# WAN.net
KiCad netlist of a schematic drawn in Altium Designer
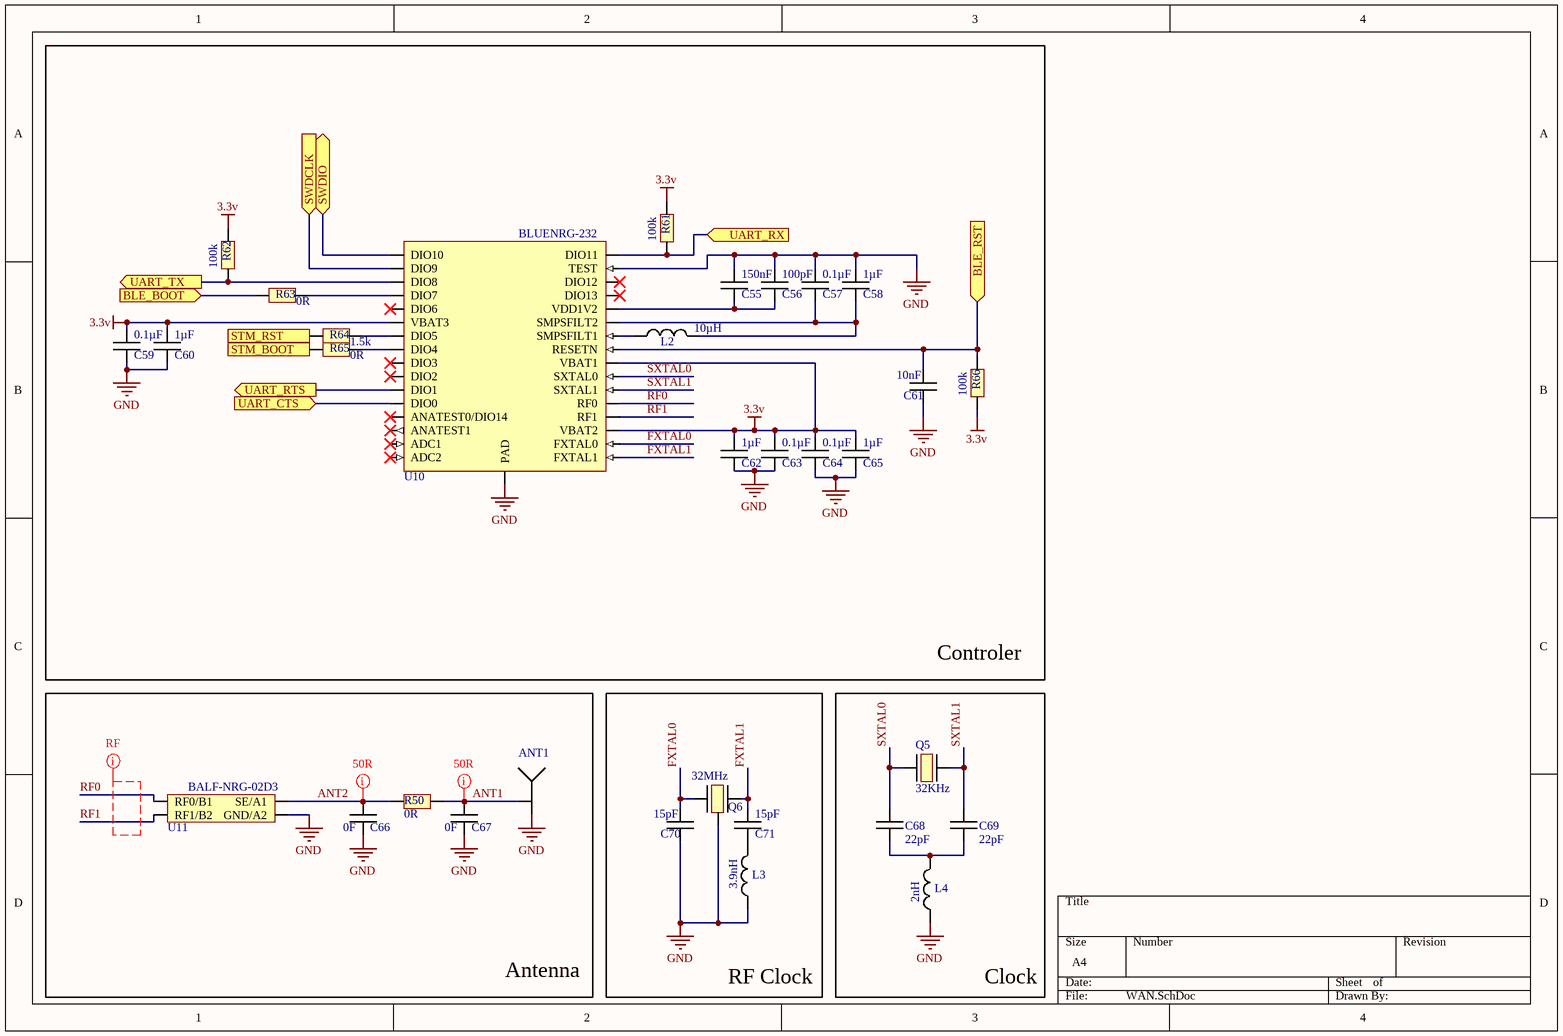
[diagram p0: WAN.SchDoc]

(export (version "E")
  (design (tool "Eeschema 10.0.6"))
  (components
    (comp (ref "ANT1") (value "UFL") (footprint "UFL") (libsource (lib "Carte_design_SCHLib") (part "UFL")))
    (comp (ref "C55")
      (value "150nF")
      (footprint "0603")
      (libsource (lib "Carte_design_SCHLib") (part "Capa"))
    )
    (comp (ref "C56")
      (value "100pF")
      (footprint "0603")
      (libsource (lib "Carte_design_SCHLib") (part "Capa"))
    )
    (comp (ref "C57")
      (value "0.1µF")
      (footprint "0603")
      (libsource (lib "Carte_design_SCHLib") (part "Capa"))
    )
    (comp (ref "C58") (value "1µF") (footprint "0603") (libsource (lib "Carte_design_SCHLib") (part "Capa")))
    (comp (ref "C59")
      (value "0.1µF")
      (footprint "0603")
      (libsource (lib "Carte_design_SCHLib") (part "Capa"))
    )
    (comp (ref "C60") (value "1µF") (footprint "0603") (libsource (lib "Carte_design_SCHLib") (part "Capa")))
    (comp (ref "C61") (value "10nF") (footprint "0603") (libsource (lib "Carte_design_SCHLib") (part "Capa")))
    (comp (ref "C62") (value "1µF") (footprint "0603") (libsource (lib "Carte_design_SCHLib") (part "Capa")))
    (comp (ref "C63")
      (value "0.1µF")
      (footprint "0603")
      (libsource (lib "Carte_design_SCHLib") (part "Capa"))
    )
    (comp (ref "C64")
      (value "0.1µF")
      (footprint "0603")
      (libsource (lib "Carte_design_SCHLib") (part "Capa"))
    )
    (comp (ref "C65") (value "1µF") (footprint "0603") (libsource (lib "Carte_design_SCHLib") (part "Capa")))
    (comp (ref "C66") (value "0F") (footprint "0603") (libsource (lib "Carte_design_SCHLib") (part "Capa")))
    (comp (ref "C67") (value "0F") (footprint "0603") (libsource (lib "Carte_design_SCHLib") (part "Capa")))
    (comp (ref "C68") (value "22pF") (footprint "0603") (libsource (lib "Carte_design_SCHLib") (part "Capa")))
    (comp (ref "C69") (value "22pF") (footprint "0603") (libsource (lib "Carte_design_SCHLib") (part "Capa")))
    (comp (ref "C70") (value "15pF") (footprint "0603") (libsource (lib "Carte_design_SCHLib") (part "Capa")))
    (comp (ref "C71") (value "15pF") (footprint "0603") (libsource (lib "Carte_design_SCHLib") (part "Capa")))
    (comp (ref "L2")
      (value "10µH")
      (footprint "0603")
      (fields (field (name "TOLERANCE") "20%"))
      (libsource (lib "Carte_design_SCHLib") (part "Self"))
    )
    (comp (ref "L3")
      (value "3.9nH")
      (footprint "0402")
      (libsource (lib "Carte_design_SCHLib") (part "self2"))
    )
    (comp (ref "L4")
      (value "2nH")
      (footprint "0603")
      (fields (field (name "TOLERANCE") "25%"))
      (libsource (lib "Carte_design_SCHLib") (part "Self"))
    )
    (comp (ref "Q5")
      (value "32KHz")
      (footprint "BLE_Quartz_Sxtal")
      (libsource (lib "Carte_design_SCHLib") (part "BLE_quartz_Sxtal"))
    )
    (comp (ref "Q6")
      (value "32MHz")
      (footprint "BLE_Quartz_Fxtal")
      (fields (field (name "TOLERANCE") "10ppm"))
      (libsource (lib "Carte_design_SCHLib") (part "BLE_Quartz_Fxtal"))
    )
    (comp (ref "R50") (value "0R") (footprint "0603") (libsource (lib "") (part "Resistance_2")))
    (comp (ref "R61")
      (value "100k")
      (footprint "0603")
      (libsource (lib "Carte_design_SCHLib") (part "Resistance"))
    )
    (comp (ref "R62")
      (value "100k")
      (footprint "0603")
      (libsource (lib "Carte_design_SCHLib") (part "Resistance"))
    )
    (comp (ref "R63") (value "0R") (footprint "0603") (libsource (lib "") (part "Resistance_1")))
    (comp (ref "R64") (value "1.5k") (footprint "0603") (libsource (lib "") (part "Resistance_1")))
    (comp (ref "R65") (value "0R") (footprint "0603") (libsource (lib "") (part "Resistance_1")))
    (comp (ref "R66")
      (value "100k")
      (footprint "0603")
      (libsource (lib "Carte_design_SCHLib") (part "Resistance"))
    )
    (comp (ref "U10")
      (value "BLUENRG-232")
      (footprint "QFN50P500X500X100_HS-33M")
      (libsource (lib "Carte_design_SCHLib") (part "BLUENRG-232"))
    )
    (comp (ref "U11")
      (value "BALF-NRG-02D3")
      (footprint "4-UFBGA")
      (libsource (lib "Carte_design_SCHLib") (part "Balf"))
    )
  )
  (nets
    (net (code "1") (name "/ANT1") (class "Default")
      (node (ref "ANT1") (pin "1") (pinfunction "GND_1") (pintype "passive"))
      (node (ref "C67") (pin "2") (pinfunction "28_2") (pintype "passive"))
      (node (ref "R50") (pin "2") (pinfunction "27_2") (pintype "passive"))
    )
    (net (code "2") (name "/ANT2") (class "Default")
      (node (ref "C66") (pin "2") (pinfunction "28_2") (pintype "passive"))
      (node (ref "R50") (pin "1") (pinfunction "26_1") (pintype "passive"))
      (node (ref "U11") (pin "1") (pinfunction "SE/A1_1") (pintype "passive"))
    )
    (net (code "3") (name "/BLE_BOOT") (class "Default")
      (node (ref "R63") (pin "2") (pinfunction "27_2") (pintype "passive"))
    )
    (net (code "4") (name "/BLE_RST") (class "Default")
      (node (ref "C61") (pin "2") (pinfunction "28_2") (pintype "passive"))
      (node (ref "R66") (pin "2") (pinfunction "27_2") (pintype "passive"))
      (node (ref "U10") (pin "25") (pinfunction "RESETN_25") (pintype "input"))
    )
    (net (code "5") (name "/FXTAL0") (class "Default")
      (node (ref "C70") (pin "2") (pinfunction "28_2") (pintype "passive"))
      (node (ref "Q6") (pin "1") (pinfunction "15_1") (pintype "passive"))
      (node (ref "U10") (pin "18") (pinfunction "FXTAL0_18") (pintype "input"))
    )
    (net (code "6") (name "/FXTAL1") (class "Default")
      (node (ref "C71") (pin "2") (pinfunction "28_2") (pintype "passive"))
      (node (ref "Q6") (pin "2") (pinfunction "16_2") (pintype "passive"))
      (node (ref "U10") (pin "17") (pinfunction "FXTAL1_17") (pintype "input"))
    )
    (net (code "7") (name "/RF0") (class "Default")
      (node (ref "U10") (pin "21") (pinfunction "RF0_21") (pintype "bidirectional"))
      (node (ref "U11") (pin "3") (pinfunction "RF0/B1_3") (pintype "passive"))
    )
    (net (code "8") (name "/RF1") (class "Default")
      (node (ref "U10") (pin "20") (pinfunction "RF1_20") (pintype "bidirectional"))
      (node (ref "U11") (pin "4") (pinfunction "RF1/B2_4") (pintype "passive"))
    )
    (net (code "9") (name "/STM_BOOT") (class "Default")
      (node (ref "R65") (pin "2") (pinfunction "27_2") (pintype "passive"))
    )
    (net (code "10") (name "/STM_RST") (class "Default")
      (node (ref "R64") (pin "2") (pinfunction "27_2") (pintype "passive"))
    )
    (net (code "11") (name "/SWDCLK") (class "Default")
      (node (ref "U10") (pin "2") (pinfunction "DIO9_2") (pintype "bidirectional"))
    )
    (net (code "12") (name "/SWDIO") (class "Default")
      (node (ref "U10") (pin "1") (pinfunction "DIO10_1") (pintype "bidirectional"))
    )
    (net (code "13") (name "/SXTAL0") (class "Default")
      (node (ref "C68") (pin "2") (pinfunction "28_2") (pintype "passive"))
      (node (ref "Q5") (pin "2") (pinfunction "16_2") (pintype "passive"))
      (node (ref "U10") (pin "23") (pinfunction "SXTAL0_23") (pintype "input"))
    )
    (net (code "14") (name "/SXTAL1") (class "Default")
      (node (ref "C69") (pin "2") (pinfunction "28_2") (pintype "passive"))
      (node (ref "Q5") (pin "1") (pinfunction "15_1") (pintype "passive"))
      (node (ref "U10") (pin "22") (pinfunction "SXTAL1_22") (pintype "input"))
    )
    (net (code "15") (name "/UART_CTS") (class "Default")
      (node (ref "U10") (pin "12") (pinfunction "DIO0_12") (pintype "bidirectional"))
    )
    (net (code "16") (name "/UART_RTS") (class "Default")
      (node (ref "U10") (pin "11") (pinfunction "DIO1_11") (pintype "bidirectional"))
    )
    (net (code "17") (name "/UART_RX") (class "Default")
      (node (ref "R61") (pin "1") (pinfunction "26_1") (pintype "passive"))
      (node (ref "U10") (pin "32") (pinfunction "DIO11_32") (pintype "bidirectional"))
    )
    (net (code "18") (name "/UART_TX") (class "Default")
      (node (ref "R62") (pin "1") (pinfunction "26_1") (pintype "passive"))
      (node (ref "U10") (pin "3") (pinfunction "DIO8_3") (pintype "bidirectional"))
    )
    (net (code "19") (name "3.3v") (class "Default")
      (node (ref "C59") (pin "2") (pinfunction "28_2") (pintype "passive"))
      (node (ref "C60") (pin "2") (pinfunction "28_2") (pintype "passive"))
      (node (ref "C62") (pin "2") (pinfunction "28_2") (pintype "passive"))
      (node (ref "C63") (pin "2") (pinfunction "28_2") (pintype "passive"))
      (node (ref "C64") (pin "2") (pinfunction "28_2") (pintype "passive"))
      (node (ref "C65") (pin "2") (pinfunction "28_2") (pintype "passive"))
      (node (ref "R61") (pin "2") (pinfunction "27_2") (pintype "passive"))
      (node (ref "R62") (pin "2") (pinfunction "27_2") (pintype "passive"))
      (node (ref "R66") (pin "1") (pinfunction "26_1") (pintype "passive"))
      (node (ref "U10") (pin "19") (pinfunction "VBAT2_19") (pintype "power_in"))
      (node (ref "U10") (pin "24") (pinfunction "VBAT1_24") (pintype "power_in"))
      (node (ref "U10") (pin "6") (pinfunction "VBAT3_6") (pintype "power_in"))
    )
    (net (code "20") (name "GND") (class "Default")
      (node (ref "ANT1") (pin "2") (pinfunction "GND_2") (pintype "passive"))
      (node (ref "C55") (pin "2") (pinfunction "28_2") (pintype "passive"))
      (node (ref "C56") (pin "2") (pinfunction "28_2") (pintype "passive"))
      (node (ref "C57") (pin "2") (pinfunction "28_2") (pintype "passive"))
      (node (ref "C58") (pin "2") (pinfunction "28_2") (pintype "passive"))
      (node (ref "C59") (pin "1") (pinfunction "29_1") (pintype "passive"))
      (node (ref "C60") (pin "1") (pinfunction "29_1") (pintype "passive"))
      (node (ref "C61") (pin "1") (pinfunction "29_1") (pintype "passive"))
      (node (ref "C62") (pin "1") (pinfunction "29_1") (pintype "passive"))
      (node (ref "C63") (pin "1") (pinfunction "29_1") (pintype "passive"))
      (node (ref "C64") (pin "1") (pinfunction "29_1") (pintype "passive"))
      (node (ref "C65") (pin "1") (pinfunction "29_1") (pintype "passive"))
      (node (ref "C66") (pin "1") (pinfunction "29_1") (pintype "passive"))
      (node (ref "C67") (pin "1") (pinfunction "29_1") (pintype "passive"))
      (node (ref "C70") (pin "1") (pinfunction "29_1") (pintype "passive"))
      (node (ref "L3") (pin "1") (pinfunction "17_1") (pintype "passive"))
      (node (ref "L4") (pin "1") (pinfunction "17_1") (pintype "passive"))
      (node (ref "Q6") (pin "3") (pinfunction "3_3") (pintype "passive"))
      (node (ref "U10") (pin "31") (pinfunction "TEST_31") (pintype "input"))
      (node (ref "U10") (pin "33") (pinfunction "PAD_33") (pintype "passive"))
      (node (ref "U11") (pin "2") (pinfunction "GND/A2_2") (pintype "passive"))
    )
    (net (code "21") (name "Net-(C55-29)") (class "Default")
      (node (ref "C55") (pin "1") (pinfunction "29_1") (pintype "passive"))
      (node (ref "C56") (pin "1") (pinfunction "29_1") (pintype "passive"))
      (node (ref "U10") (pin "28") (pinfunction "VDD1V2_28") (pintype "power_in"))
    )
    (net (code "22") (name "Net-(C57-29)") (class "Default")
      (node (ref "C57") (pin "1") (pinfunction "29_1") (pintype "passive"))
      (node (ref "C58") (pin "1") (pinfunction "29_1") (pintype "passive"))
      (node (ref "L2") (pin "2") (pinfunction "18_2") (pintype "passive"))
      (node (ref "U10") (pin "27") (pinfunction "SMPSFILT2_27") (pintype "bidirectional"))
    )
    (net (code "23") (name "Net-(C68-29)") (class "Default")
      (node (ref "C68") (pin "1") (pinfunction "29_1") (pintype "passive"))
      (node (ref "C69") (pin "1") (pinfunction "29_1") (pintype "passive"))
      (node (ref "L4") (pin "2") (pinfunction "18_2") (pintype "passive"))
    )
    (net (code "24") (name "Net-(C71-29)") (class "Default")
      (node (ref "C71") (pin "1") (pinfunction "29_1") (pintype "passive"))
      (node (ref "L3") (pin "2") (pinfunction "18_2") (pintype "passive"))
    )
    (net (code "25") (name "Net-(L2-17)") (class "Default")
      (node (ref "L2") (pin "1") (pinfunction "17_1") (pintype "passive"))
      (node (ref "U10") (pin "26") (pinfunction "SMPSFILT1_26") (pintype "input"))
    )
    (net (code "26") (name "Net-(R63-26)") (class "Default")
      (node (ref "R63") (pin "1") (pinfunction "26_1") (pintype "passive"))
      (node (ref "U10") (pin "4") (pinfunction "DIO7_4") (pintype "bidirectional"))
    )
    (net (code "27") (name "Net-(R64-26)") (class "Default")
      (node (ref "R64") (pin "1") (pinfunction "26_1") (pintype "passive"))
      (node (ref "U10") (pin "7") (pinfunction "DIO5_7") (pintype "bidirectional"))
    )
    (net (code "28") (name "Net-(R65-26)") (class "Default")
      (node (ref "R65") (pin "1") (pinfunction "26_1") (pintype "passive"))
      (node (ref "U10") (pin "8") (pinfunction "DIO4_8") (pintype "bidirectional"))
    )
    (net (code "29") (name "unconnected-(U10-ADC1-Pad15)") (class "Default")
      (node (ref "U10") (pin "15") (pinfunction "ADC1_15") (pintype "input+no_connect"))
    )
    (net (code "30") (name "unconnected-(U10-ADC2-Pad16)") (class "Default")
      (node (ref "U10") (pin "16") (pinfunction "ADC2_16") (pintype "input+no_connect"))
    )
    (net (code "31") (name "unconnected-(U10-ANATEST0{slash}DIO14-Pad13)") (class "Default")
      (node (ref "U10") (pin "13") (pinfunction "ANATEST0/DIO14_13") (pintype "bidirectional+no_connect"))
    )
    (net (code "32") (name "unconnected-(U10-ANATEST1-Pad14)") (class "Default")
      (node (ref "U10") (pin "14") (pinfunction "ANATEST1_14") (pintype "output+no_connect"))
    )
    (net (code "33") (name "unconnected-(U10-DIO2-Pad10)") (class "Default")
      (node (ref "U10") (pin "10") (pinfunction "DIO2_10") (pintype "bidirectional+no_connect"))
    )
    (net (code "34") (name "unconnected-(U10-DIO3-Pad9)") (class "Default")
      (node (ref "U10") (pin "9") (pinfunction "DIO3_9") (pintype "bidirectional+no_connect"))
    )
    (net (code "35") (name "unconnected-(U10-DIO6-Pad5)") (class "Default")
      (node (ref "U10") (pin "5") (pinfunction "DIO6_5") (pintype "bidirectional+no_connect"))
    )
    (net (code "36") (name "unconnected-(U10-DIO12-Pad30)") (class "Default")
      (node (ref "U10") (pin "30") (pinfunction "DIO12_30") (pintype "bidirectional+no_connect"))
    )
    (net (code "37") (name "unconnected-(U10-DIO13-Pad29)") (class "Default")
      (node (ref "U10") (pin "29") (pinfunction "DIO13_29") (pintype "bidirectional+no_connect"))
    )
  )
)
